# V0p2_Main_PCB2.net
KiCad netlist of a schematic drawn in EAGLE
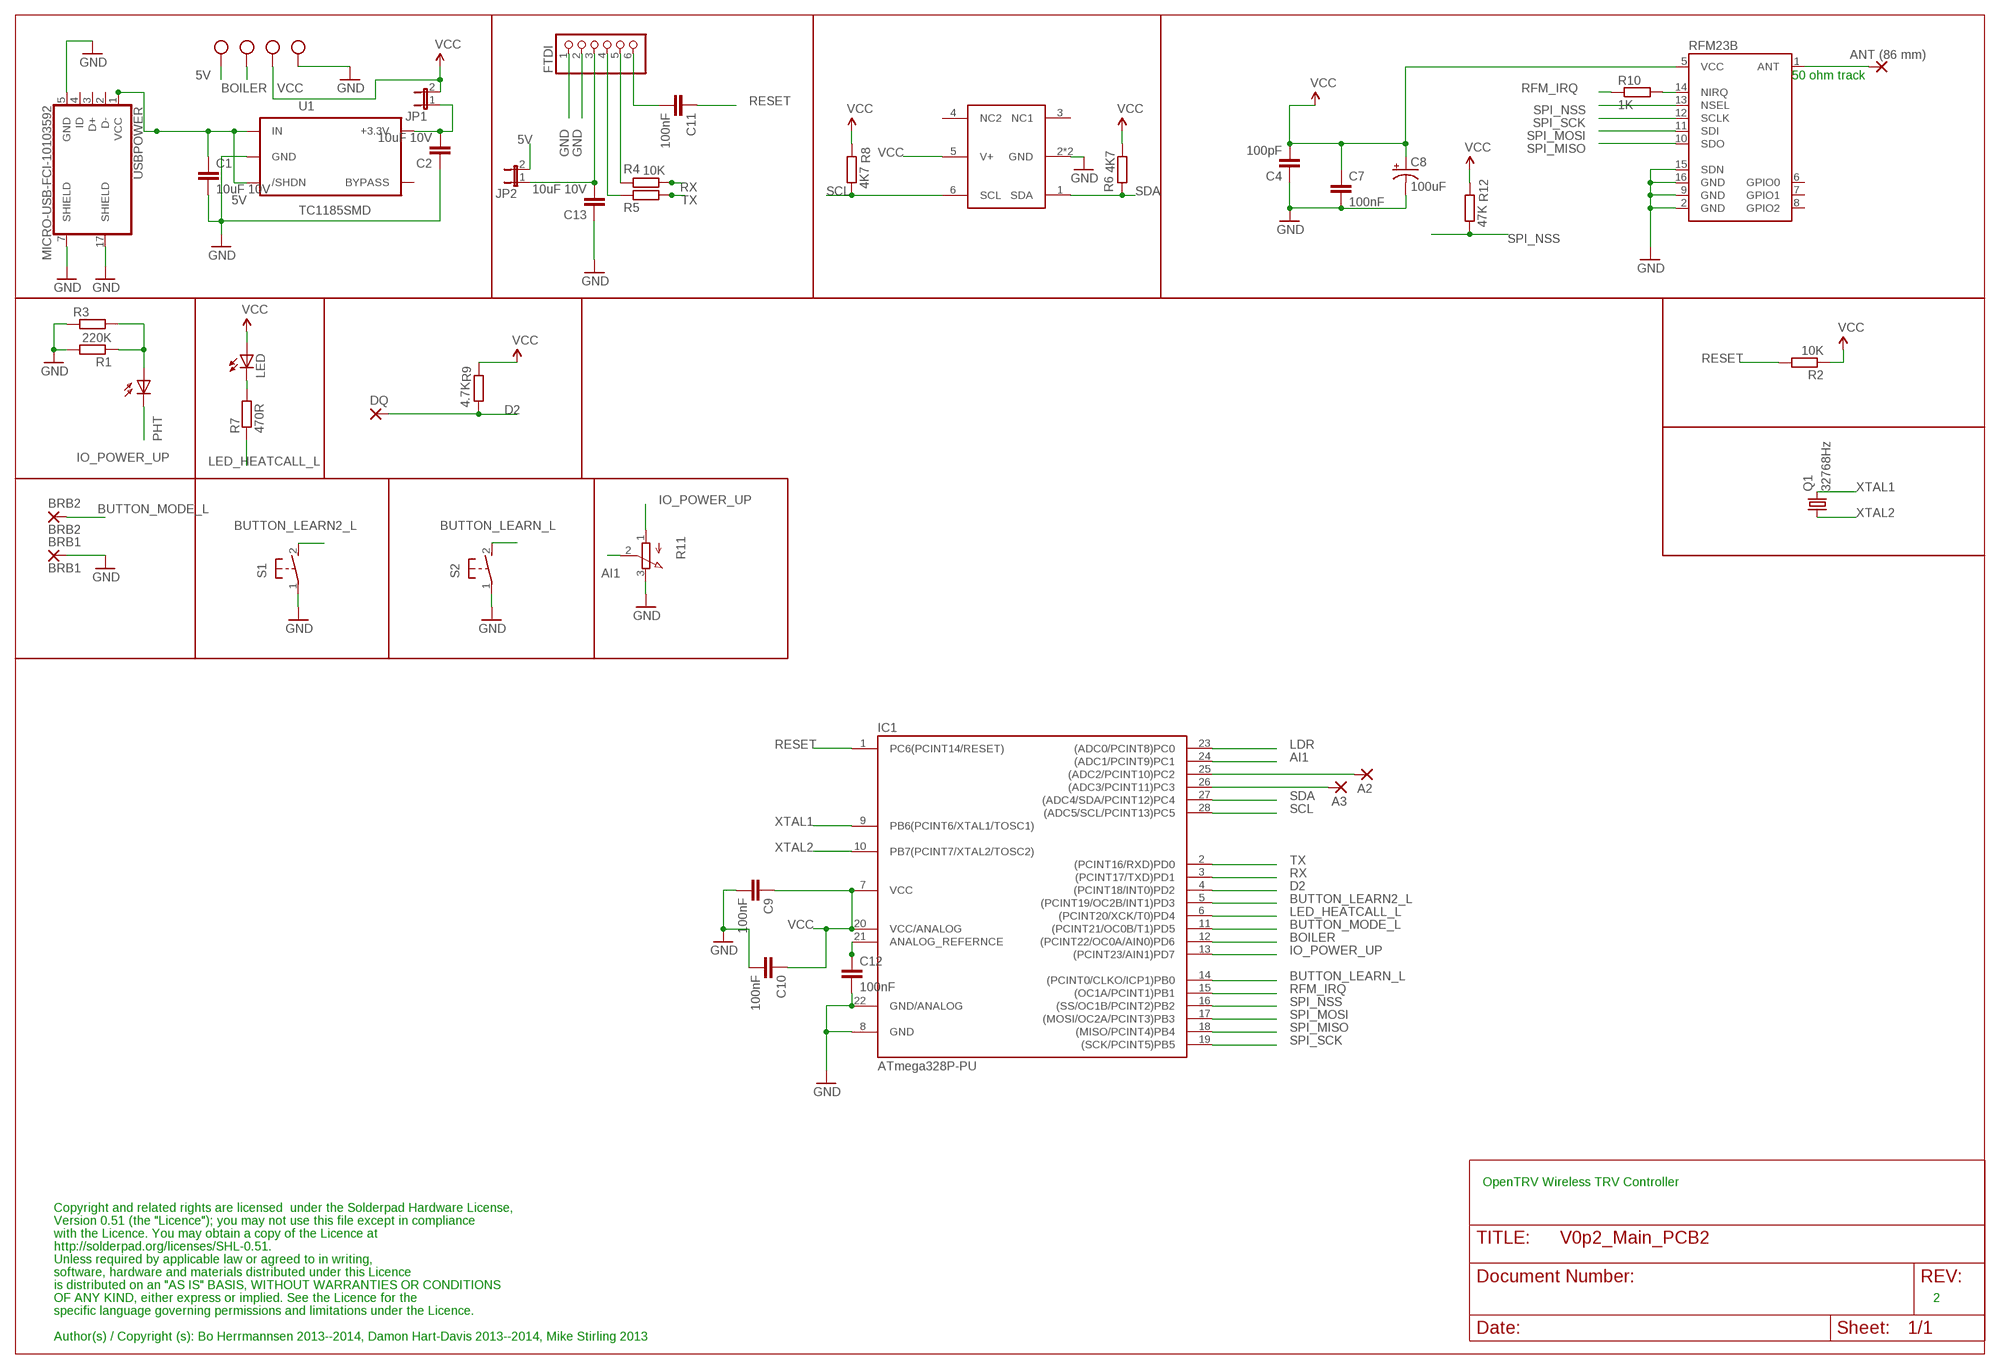
[diagram p0: schematic, sheet 1]

(export (version "E")
  (design (tool "Eeschema 10.0.6"))
  (components
    (comp (ref "A2")
      (value "2,15/1,0")
      (footprint "eagle-import:2,15_1,0")
      (libsource (lib "eagle-import") (part "2,15/1,0"))
    )
    (comp (ref "A3")
      (value "2,15/1,0")
      (footprint "eagle-import:2,15_1,0")
      (libsource (lib "eagle-import") (part "2,15/1,0"))
    )
    (comp (ref "ANT1")
      (value "ANT (86 mm)")
      (footprint "eagle-import:2,15_1,0")
      (libsource (lib "eagle-import") (part "2,15/1,0"))
    )
    (comp (ref "BRB1")
      (value "BRB1")
      (footprint "eagle-import:2,15_1,0")
      (libsource (lib "eagle-import") (part "2,15/1,0"))
    )
    (comp (ref "BRB2")
      (value "BRB2")
      (footprint "eagle-import:2,15_1,0")
      (libsource (lib "eagle-import") (part "2,15/1,0"))
    )
    (comp (ref "C1")
      (value "10uF 10V")
      (footprint "eagle-import:C0603")
      (libsource (lib "eagle-import") (part "C-EUC0603"))
    )
    (comp (ref "C2")
      (value "10uF 10V")
      (footprint "eagle-import:C0603")
      (libsource (lib "eagle-import") (part "C-EUC0603"))
    )
    (comp (ref "C4")
      (value "100pF")
      (footprint "eagle-import:C0603")
      (libsource (lib "eagle-import") (part "C-EUC0603"))
    )
    (comp (ref "C7")
      (value "100nF")
      (footprint "eagle-import:C0603")
      (libsource (lib "eagle-import") (part "C-EUC0603"))
    )
    (comp (ref "C8")
      (value "100uF")
      (footprint "eagle-import:EIA3216")
      (libsource (lib "eagle-import") (part "CAP_POL1206"))
    )
    (comp (ref "C9")
      (value "100nF")
      (footprint "eagle-import:C0603")
      (libsource (lib "eagle-import") (part "C-EUC0603"))
    )
    (comp (ref "C10")
      (value "100nF")
      (footprint "eagle-import:C0603")
      (libsource (lib "eagle-import") (part "C-EUC0603"))
    )
    (comp (ref "C11")
      (value "100nF")
      (footprint "eagle-import:C0603")
      (libsource (lib "eagle-import") (part "C-EUC0603"))
    )
    (comp (ref "C12")
      (value "100nF")
      (footprint "eagle-import:C0603")
      (libsource (lib "eagle-import") (part "C-EUC0603"))
    )
    (comp (ref "C13")
      (value "10uF 10V")
      (footprint "eagle-import:C0603")
      (libsource (lib "eagle-import") (part "C-EUC0603"))
    )
    (comp (ref "DQ")
      (value "2,15/1,0")
      (footprint "eagle-import:2,15_1,0")
      (libsource (lib "eagle-import") (part "2,15/1,0"))
    )
    (comp (ref "FTDI")
      (value "PINHD-1X6/90")
      (footprint "eagle-import:1X06_90")
      (libsource (lib "eagle-import") (part "PINHD-1X6/90"))
    )
    (comp (ref "IC1")
      (value "ATmega328P-PU")
      (footprint "eagle-import:DIL28-3")
      (libsource (lib "eagle-import") (part "ATMEGA168-PU"))
    )
    (comp (ref "JP1")
      (value "JP1E")
      (footprint "eagle-import:JP1")
      (libsource (lib "eagle-import") (part "JP1E"))
    )
    (comp (ref "JP2")
      (value "JP1E")
      (footprint "eagle-import:JP1")
      (libsource (lib "eagle-import") (part "JP1E"))
    )
    (comp (ref "LED")
      (value "LED3MM")
      (footprint "eagle-import:LED3MM")
      (libsource (lib "eagle-import") (part "LED3MM"))
    )
    (comp (ref "PHT")
      (value "BPX65")
      (footprint "eagle-import:BPX65")
      (fields (field (name "MPN") "BPX65."))
      (libsource (lib "eagle-import") (part "BPX65"))
    )
    (comp (ref "Q1")
      (value "32768Hz")
      (footprint "eagle-import:MC-306")
      (fields (field (name "MPN") "MC-306 60.0KHZ  100PPM ,12.5PF"))
      (libsource (lib "eagle-import") (part "MC-306"))
    )
    (comp (ref "R1")
      (value "220K")
      (footprint "eagle-import:R0603")
      (libsource (lib "eagle-import") (part "R-EU_R0603"))
    )
    (comp (ref "R2")
      (value "10K")
      (footprint "eagle-import:R0603")
      (libsource (lib "eagle-import") (part "R-EU_R0603"))
    )
    (comp (ref "R3")
      (value "R-EU_0309/V")
      (footprint "eagle-import:0309V")
      (libsource (lib "eagle-import") (part "R-EU_0309/V"))
    )
    (comp (ref "R4")
      (value "10K")
      (footprint "eagle-import:R0603")
      (libsource (lib "eagle-import") (part "R-EU_R0603"))
    )
    (comp (ref "R5")
      (value "10K")
      (footprint "eagle-import:R0603")
      (libsource (lib "eagle-import") (part "R-EU_R0603"))
    )
    (comp (ref "R6")
      (value "4K7")
      (footprint "eagle-import:R0603")
      (libsource (lib "eagle-import") (part "R-EU_R0603"))
    )
    (comp (ref "R7")
      (value "470R")
      (footprint "eagle-import:R0603")
      (libsource (lib "eagle-import") (part "R-EU_R0603"))
    )
    (comp (ref "R8")
      (value "4K7")
      (footprint "eagle-import:R0603")
      (libsource (lib "eagle-import") (part "R-EU_R0603"))
    )
    (comp (ref "R9")
      (value "4.7K")
      (footprint "eagle-import:R0603")
      (libsource (lib "eagle-import") (part "R-EU_R0603"))
    )
    (comp (ref "R10")
      (value "1K")
      (footprint "eagle-import:R0603")
      (libsource (lib "eagle-import") (part "R-EU_R0603"))
    )
    (comp (ref "R11")
      (value "EVUE2A")
      (footprint "eagle-import:EVUE")
      (libsource (lib "eagle-import") (part "EVUE2A"))
    )
    (comp (ref "R12")
      (value "47K")
      (footprint "eagle-import:R0603")
      (libsource (lib "eagle-import") (part "R-EU_R0603"))
    )
    (comp (ref "RFM23B")
      (value "RFM23B")
      (footprint "eagle-import:RFM23-XXX-S1")
      (libsource (lib "eagle-import") (part "RFM23B"))
    )
    (comp (ref "S1")
      (value "31-XX")
      (footprint "eagle-import:B3F-31XX")
      (libsource (lib "eagle-import") (part "31-XX"))
    )
    (comp (ref "S2")
      (value "31-XX")
      (footprint "eagle-import:B3F-31XX")
      (libsource (lib "eagle-import") (part "31-XX"))
    )
    (comp (ref "U$4")
      (value "SHT21")
      (footprint "eagle-import:SHT21")
      (libsource (lib "eagle-import") (part "SHT21"))
    )
    (comp (ref "U1")
      (value "TC1185SMD")
      (footprint "eagle-import:TC1185")
      (libsource (lib "eagle-import") (part "TC1185SMD"))
    )
    (comp (ref "USBPOWER")
      (value "MICRO-USB-FCI-10103592")
      (footprint "eagle-import:MICRO-USB-FCI-10103592")
      (libsource (lib "eagle-import") (part "MICRO-USB-FCI-10103592"))
    )
    (comp (ref "X1")
      (value "W237-102")
      (footprint "eagle-import:SCREWTERMINAL")
      (fields (field (name "MPN") "237-102"))
      (libsource (lib "eagle-import") (part "W237-102"))
    )
    (comp (ref "X2")
      (value "W237-102")
      (footprint "eagle-import:SCREWTERMINAL")
      (fields (field (name "MPN") "237-102"))
      (libsource (lib "eagle-import") (part "W237-102"))
    )
  )
  (nets
    (net (code "1") (name "/5V") (class "Default")
      (node (ref "C1") (pin "1") (pinfunction "1_1") (pintype "passive"))
      (node (ref "JP2") (pin "2") (pinfunction "2_2") (pintype "passive"))
      (node (ref "U1") (pin "1") (pinfunction "IN_1") (pintype "passive"))
      (node (ref "U1") (pin "3") (pinfunction "/SHDN_3") (pintype "passive"))
      (node (ref "USBPOWER") (pin "1") (pinfunction "VCC_1") (pintype "bidirectional"))
      (node (ref "X1") (pin "2") (pinfunction "KL_2") (pintype "passive"))
    )
    (net (code "2") (name "/AI1") (class "Default")
      (node (ref "IC1") (pin "24") (pinfunction "(ADC1/PCINT9)PC1_24") (pintype "bidirectional"))
      (node (ref "R11") (pin "2") (pinfunction "S_2") (pintype "passive"))
    )
    (net (code "3") (name "/BOILER") (class "Default")
      (node (ref "IC1") (pin "12") (pinfunction "(PCINT22/OC0A/AIN0)PD6_12") (pintype "bidirectional"))
      (node (ref "X1") (pin "1") (pinfunction "KL_1") (pintype "passive"))
    )
    (net (code "4") (name "/BUTTON_LEARN2_L") (class "Default")
      (node (ref "IC1") (pin "5") (pinfunction "(PCINT19/OC2B/INT1)PD3_5") (pintype "bidirectional"))
      (node (ref "S1") (pin "2") (pinfunction "S_2") (pintype "passive"))
    )
    (net (code "5") (name "/BUTTON_LEARN_L") (class "Default")
      (node (ref "IC1") (pin "14") (pinfunction "(PCINT0/CLKO/ICP1)PB0_14") (pintype "bidirectional"))
      (node (ref "S2") (pin "2") (pinfunction "S_2") (pintype "passive"))
    )
    (net (code "6") (name "/BUTTON_MODE_L") (class "Default")
      (node (ref "BRB2") (pin "1") (pinfunction "P_1") (pintype "passive"))
      (node (ref "IC1") (pin "11") (pinfunction "(PCINT21/OC0B/T1)PD5_11") (pintype "bidirectional"))
    )
    (net (code "7") (name "/D2") (class "Default")
      (node (ref "DQ") (pin "1") (pinfunction "P_1") (pintype "passive"))
      (node (ref "IC1") (pin "4") (pinfunction "(PCINT18/INT0)PD2_4") (pintype "bidirectional"))
      (node (ref "R9") (pin "1") (pinfunction "1_1") (pintype "passive"))
    )
    (net (code "8") (name "/IO_POWER_UP") (class "Default")
      (node (ref "IC1") (pin "13") (pinfunction "(PCINT23/AIN1)PD7_13") (pintype "bidirectional"))
      (node (ref "PHT") (pin "K") (pinfunction "C_K") (pintype "passive"))
      (node (ref "R11") (pin "1") (pinfunction "A_1") (pintype "passive"))
    )
    (net (code "9") (name "/LDR") (class "Default")
      (node (ref "IC1") (pin "23") (pinfunction "(ADC0/PCINT8)PC0_23") (pintype "bidirectional"))
      (node (ref "PHT") (pin "A") (pinfunction "A_A") (pintype "passive"))
      (node (ref "R1") (pin "1") (pinfunction "1_1") (pintype "passive"))
      (node (ref "R3") (pin "2") (pinfunction "2_2") (pintype "passive"))
    )
    (net (code "10") (name "/LED_HEATCALL_L") (class "Default")
      (node (ref "IC1") (pin "6") (pinfunction "(PCINT20/XCK/T0)PD4_6") (pintype "bidirectional"))
      (node (ref "R7") (pin "1") (pinfunction "1_1") (pintype "passive"))
    )
    (net (code "11") (name "/RESET") (class "Default")
      (node (ref "C11") (pin "1") (pinfunction "1_1") (pintype "passive"))
      (node (ref "IC1") (pin "1") (pinfunction "PC6(PCINT14/RESET)_1") (pintype "bidirectional"))
      (node (ref "R2") (pin "2") (pinfunction "2_2") (pintype "passive"))
    )
    (net (code "12") (name "/RFM_IRQ") (class "Default")
      (node (ref "IC1") (pin "15") (pinfunction "(OC1A/PCINT1)PB1_15") (pintype "bidirectional"))
      (node (ref "R10") (pin "1") (pinfunction "1_1") (pintype "passive"))
    )
    (net (code "13") (name "/RX") (class "Default")
      (node (ref "IC1") (pin "3") (pinfunction "(PCINT17/TXD)PD1_3") (pintype "bidirectional"))
      (node (ref "R4") (pin "1") (pinfunction "1_1") (pintype "passive"))
    )
    (net (code "14") (name "/SCL") (class "Default")
      (node (ref "IC1") (pin "28") (pinfunction "(ADC5/SCL/PCINT13)PC5_28") (pintype "bidirectional"))
      (node (ref "R8") (pin "1") (pinfunction "1_1") (pintype "passive"))
      (node (ref "U$4") (pin "6") (pinfunction "SCL_6") (pintype "bidirectional"))
    )
    (net (code "15") (name "/SDA") (class "Default")
      (node (ref "IC1") (pin "27") (pinfunction "(ADC4/SDA/PCINT12)PC4_27") (pintype "bidirectional"))
      (node (ref "R6") (pin "2") (pinfunction "2_2") (pintype "passive"))
      (node (ref "U$4") (pin "1") (pinfunction "SDA_1") (pintype "bidirectional"))
    )
    (net (code "16") (name "/SPI_MISO") (class "Default")
      (node (ref "IC1") (pin "18") (pinfunction "(MISO/PCINT4)PB4_18") (pintype "bidirectional"))
      (node (ref "RFM23B") (pin "10") (pinfunction "SDO_10") (pintype "output"))
    )
    (net (code "17") (name "/SPI_MOSI") (class "Default")
      (node (ref "IC1") (pin "17") (pinfunction "(MOSI/OC2A/PCINT3)PB3_17") (pintype "bidirectional"))
      (node (ref "RFM23B") (pin "11") (pinfunction "SDI_11") (pintype "input"))
    )
    (net (code "18") (name "/SPI_NSS") (class "Default")
      (node (ref "IC1") (pin "16") (pinfunction "(SS/OC1B/PCINT2)PB2_16") (pintype "bidirectional"))
      (node (ref "R12") (pin "1") (pinfunction "1_1") (pintype "passive"))
      (node (ref "RFM23B") (pin "13") (pinfunction "NSEL_13") (pintype "input"))
    )
    (net (code "19") (name "/SPI_SCK") (class "Default")
      (node (ref "IC1") (pin "19") (pinfunction "(SCK/PCINT5)PB5_19") (pintype "bidirectional"))
      (node (ref "RFM23B") (pin "12") (pinfunction "SCLK_12") (pintype "input"))
    )
    (net (code "20") (name "/TX") (class "Default")
      (node (ref "IC1") (pin "2") (pinfunction "(PCINT16/RXD)PD0_2") (pintype "bidirectional"))
      (node (ref "R5") (pin "1") (pinfunction "1_1") (pintype "passive"))
    )
    (net (code "21") (name "/XTAL1") (class "Default")
      (node (ref "IC1") (pin "9") (pinfunction "PB6(PCINT6/XTAL1/TOSC1)_9") (pintype "bidirectional"))
      (node (ref "Q1") (pin "4") (pinfunction "2_4") (pintype "passive"))
    )
    (net (code "22") (name "/XTAL2") (class "Default")
      (node (ref "IC1") (pin "10") (pinfunction "PB7(PCINT7/XTAL2/TOSC2)_10") (pintype "bidirectional"))
      (node (ref "Q1") (pin "1") (pinfunction "1_1") (pintype "passive"))
    )
    (net (code "23") (name "GND") (class "Default")
      (node (ref "BRB1") (pin "1") (pinfunction "P_1") (pintype "passive"))
      (node (ref "C1") (pin "2") (pinfunction "2_2") (pintype "passive"))
      (node (ref "C10") (pin "2") (pinfunction "2_2") (pintype "passive"))
      (node (ref "C12") (pin "2") (pinfunction "2_2") (pintype "passive"))
      (node (ref "C13") (pin "1") (pinfunction "1_1") (pintype "passive"))
      (node (ref "C2") (pin "1") (pinfunction "1_1") (pintype "passive"))
      (node (ref "C4") (pin "1") (pinfunction "1_1") (pintype "passive"))
      (node (ref "C7") (pin "2") (pinfunction "2_2") (pintype "passive"))
      (node (ref "C8") (pin "C") (pinfunction "-_C") (pintype "passive"))
      (node (ref "C9") (pin "2") (pinfunction "2_2") (pintype "passive"))
      (node (ref "FTDI") (pin "1") (pinfunction "1_1") (pintype "passive"))
      (node (ref "FTDI") (pin "2") (pinfunction "2_2") (pintype "passive"))
      (node (ref "IC1") (pin "22") (pinfunction "GND/ANALOG_22") (pintype "power_in"))
      (node (ref "IC1") (pin "8") (pinfunction "GND_8") (pintype "power_in"))
      (node (ref "R1") (pin "2") (pinfunction "2_2") (pintype "passive"))
      (node (ref "R11") (pin "3") (pinfunction "E_3") (pintype "passive"))
      (node (ref "R3") (pin "1") (pinfunction "1_1") (pintype "passive"))
      (node (ref "RFM23B") (pin "15") (pinfunction "SDN_15") (pintype "input"))
      (node (ref "RFM23B") (pin "16") (pinfunction "GND_16") (pintype "power_in"))
      (node (ref "RFM23B") (pin "2") (pinfunction "GND_2") (pintype "power_in"))
      (node (ref "RFM23B") (pin "9") (pinfunction "GND_9") (pintype "power_in"))
      (node (ref "S1") (pin "1") (pinfunction "P_1") (pintype "passive"))
      (node (ref "S2") (pin "1") (pinfunction "P_1") (pintype "passive"))
      (node (ref "U$4") (pin "2") (pinfunction "GND_2") (pintype "bidirectional"))
      (node (ref "U$4") (pin "P$1") (pinfunction "GND_P$1") (pintype "bidirectional"))
      (node (ref "U1") (pin "2") (pinfunction "GND_2") (pintype "passive"))
      (node (ref "USBPOWER") (pin "17") (pinfunction "SHIELD_17") (pintype "bidirectional"))
      (node (ref "USBPOWER") (pin "5") (pinfunction "GND_5") (pintype "bidirectional"))
      (node (ref "USBPOWER") (pin "7") (pinfunction "SHIELD_7") (pintype "bidirectional"))
      (node (ref "X2") (pin "2") (pinfunction "KL_2") (pintype "passive"))
    )
    (net (code "24") (name "Net-(A2-P)") (class "Default")
      (node (ref "A2") (pin "1") (pinfunction "P_1") (pintype "passive"))
      (node (ref "IC1") (pin "25") (pinfunction "(ADC2/PCINT10)PC2_25") (pintype "bidirectional"))
    )
    (net (code "25") (name "Net-(A3-P)") (class "Default")
      (node (ref "A3") (pin "1") (pinfunction "P_1") (pintype "passive"))
      (node (ref "IC1") (pin "26") (pinfunction "(ADC3/PCINT11)PC3_26") (pintype "bidirectional"))
    )
    (net (code "26") (name "Net-(ANT1-P)") (class "Default")
      (node (ref "ANT1") (pin "1") (pinfunction "P_1") (pintype "passive"))
      (node (ref "RFM23B") (pin "1") (pinfunction "ANT_1") (pintype "bidirectional"))
    )
    (net (code "27") (name "Net-(C11-Pad2)") (class "Default")
      (node (ref "C11") (pin "2") (pinfunction "2_2") (pintype "passive"))
      (node (ref "FTDI") (pin "6") (pinfunction "6_6") (pintype "passive"))
    )
    (net (code "28") (name "Net-(C13-Pad2)") (class "Default")
      (node (ref "C13") (pin "2") (pinfunction "2_2") (pintype "passive"))
      (node (ref "FTDI") (pin "3") (pinfunction "3_3") (pintype "passive"))
      (node (ref "JP2") (pin "1") (pinfunction "1_1") (pintype "passive"))
    )
    (net (code "29") (name "Net-(FTDI-Pad4)") (class "Default")
      (node (ref "FTDI") (pin "4") (pinfunction "4_4") (pintype "passive"))
      (node (ref "R5") (pin "2") (pinfunction "2_2") (pintype "passive"))
    )
    (net (code "30") (name "Net-(FTDI-Pad5)") (class "Default")
      (node (ref "FTDI") (pin "5") (pinfunction "5_5") (pintype "passive"))
      (node (ref "R4") (pin "2") (pinfunction "2_2") (pintype "passive"))
    )
    (net (code "31") (name "Net-(IC1-ANALOG_REFERNCE)") (class "Default")
      (node (ref "C12") (pin "1") (pinfunction "1_1") (pintype "passive"))
      (node (ref "IC1") (pin "21") (pinfunction "ANALOG_REFERNCE_21") (pintype "passive"))
    )
    (net (code "32") (name "Net-(LED-C)") (class "Default")
      (node (ref "LED") (pin "K") (pinfunction "C_K") (pintype "passive"))
      (node (ref "R7") (pin "2") (pinfunction "2_2") (pintype "passive"))
    )
    (net (code "33") (name "Net-(RFM23B-NIRQ)") (class "Default")
      (node (ref "R10") (pin "2") (pinfunction "2_2") (pintype "passive"))
      (node (ref "RFM23B") (pin "14") (pinfunction "NIRQ_14") (pintype "output"))
    )
    (net (code "34") (name "Net-(U1-+3.3V)") (class "Default")
      (node (ref "C2") (pin "2") (pinfunction "2_2") (pintype "passive"))
      (node (ref "JP1") (pin "1") (pinfunction "1_1") (pintype "passive"))
      (node (ref "U1") (pin "5") (pinfunction "+3.3V_5") (pintype "power_in"))
    )
    (net (code "35") (name "VCC") (class "Default")
      (node (ref "C10") (pin "1") (pinfunction "1_1") (pintype "passive"))
      (node (ref "C4") (pin "2") (pinfunction "2_2") (pintype "passive"))
      (node (ref "C7") (pin "1") (pinfunction "1_1") (pintype "passive"))
      (node (ref "C8") (pin "A") (pinfunction "+_A") (pintype "passive"))
      (node (ref "C9") (pin "1") (pinfunction "1_1") (pintype "passive"))
      (node (ref "IC1") (pin "20") (pinfunction "VCC/ANALOG_20") (pintype "passive"))
      (node (ref "IC1") (pin "7") (pinfunction "VCC_7") (pintype "power_in"))
      (node (ref "JP1") (pin "2") (pinfunction "2_2") (pintype "passive"))
      (node (ref "LED") (pin "A") (pinfunction "A_A") (pintype "passive"))
      (node (ref "R12") (pin "2") (pinfunction "2_2") (pintype "passive"))
      (node (ref "R2") (pin "1") (pinfunction "1_1") (pintype "passive"))
      (node (ref "R6") (pin "1") (pinfunction "1_1") (pintype "passive"))
      (node (ref "R8") (pin "2") (pinfunction "2_2") (pintype "passive"))
      (node (ref "R9") (pin "2") (pinfunction "2_2") (pintype "passive"))
      (node (ref "RFM23B") (pin "5") (pinfunction "VCC_5") (pintype "bidirectional"))
      (node (ref "U$4") (pin "5") (pinfunction "V+_5") (pintype "bidirectional"))
      (node (ref "X2") (pin "1") (pinfunction "KL_1") (pintype "passive"))
    )
    (net (code "36") (name "unconnected-(RFM23B-GPIO0-Pad6)") (class "Default")
      (node (ref "RFM23B") (pin "6") (pinfunction "GPIO0_6") (pintype "bidirectional"))
    )
    (net (code "37") (name "unconnected-(RFM23B-GPIO1-Pad7)") (class "Default")
      (node (ref "RFM23B") (pin "7") (pinfunction "GPIO1_7") (pintype "bidirectional"))
    )
    (net (code "38") (name "unconnected-(RFM23B-GPIO2-Pad8)") (class "Default")
      (node (ref "RFM23B") (pin "8") (pinfunction "GPIO2_8") (pintype "bidirectional"))
    )
    (net (code "39") (name "unconnected-(U$4-NC1-Pad3)") (class "Default")
      (node (ref "U$4") (pin "3") (pinfunction "NC1_3") (pintype "bidirectional"))
    )
    (net (code "40") (name "unconnected-(U$4-NC2-Pad4)") (class "Default")
      (node (ref "U$4") (pin "4") (pinfunction "NC2_4") (pintype "bidirectional"))
    )
    (net (code "41") (name "unconnected-(U1-BYPASS-Pad4)") (class "Default")
      (node (ref "U1") (pin "4") (pinfunction "BYPASS_4") (pintype "passive"))
    )
    (net (code "42") (name "unconnected-(USBPOWER-D+-Pad3)") (class "Default")
      (node (ref "USBPOWER") (pin "3") (pinfunction "D+_3") (pintype "bidirectional"))
    )
    (net (code "43") (name "unconnected-(USBPOWER-D--Pad2)") (class "Default")
      (node (ref "USBPOWER") (pin "2") (pinfunction "D-_2") (pintype "bidirectional"))
    )
    (net (code "44") (name "unconnected-(USBPOWER-ID-Pad4)") (class "Default")
      (node (ref "USBPOWER") (pin "4") (pinfunction "ID_4") (pintype "bidirectional"))
    )
  )
)
